# 06_SOM_Console.net
KiCad netlist of a schematic drawn in Altium Designer
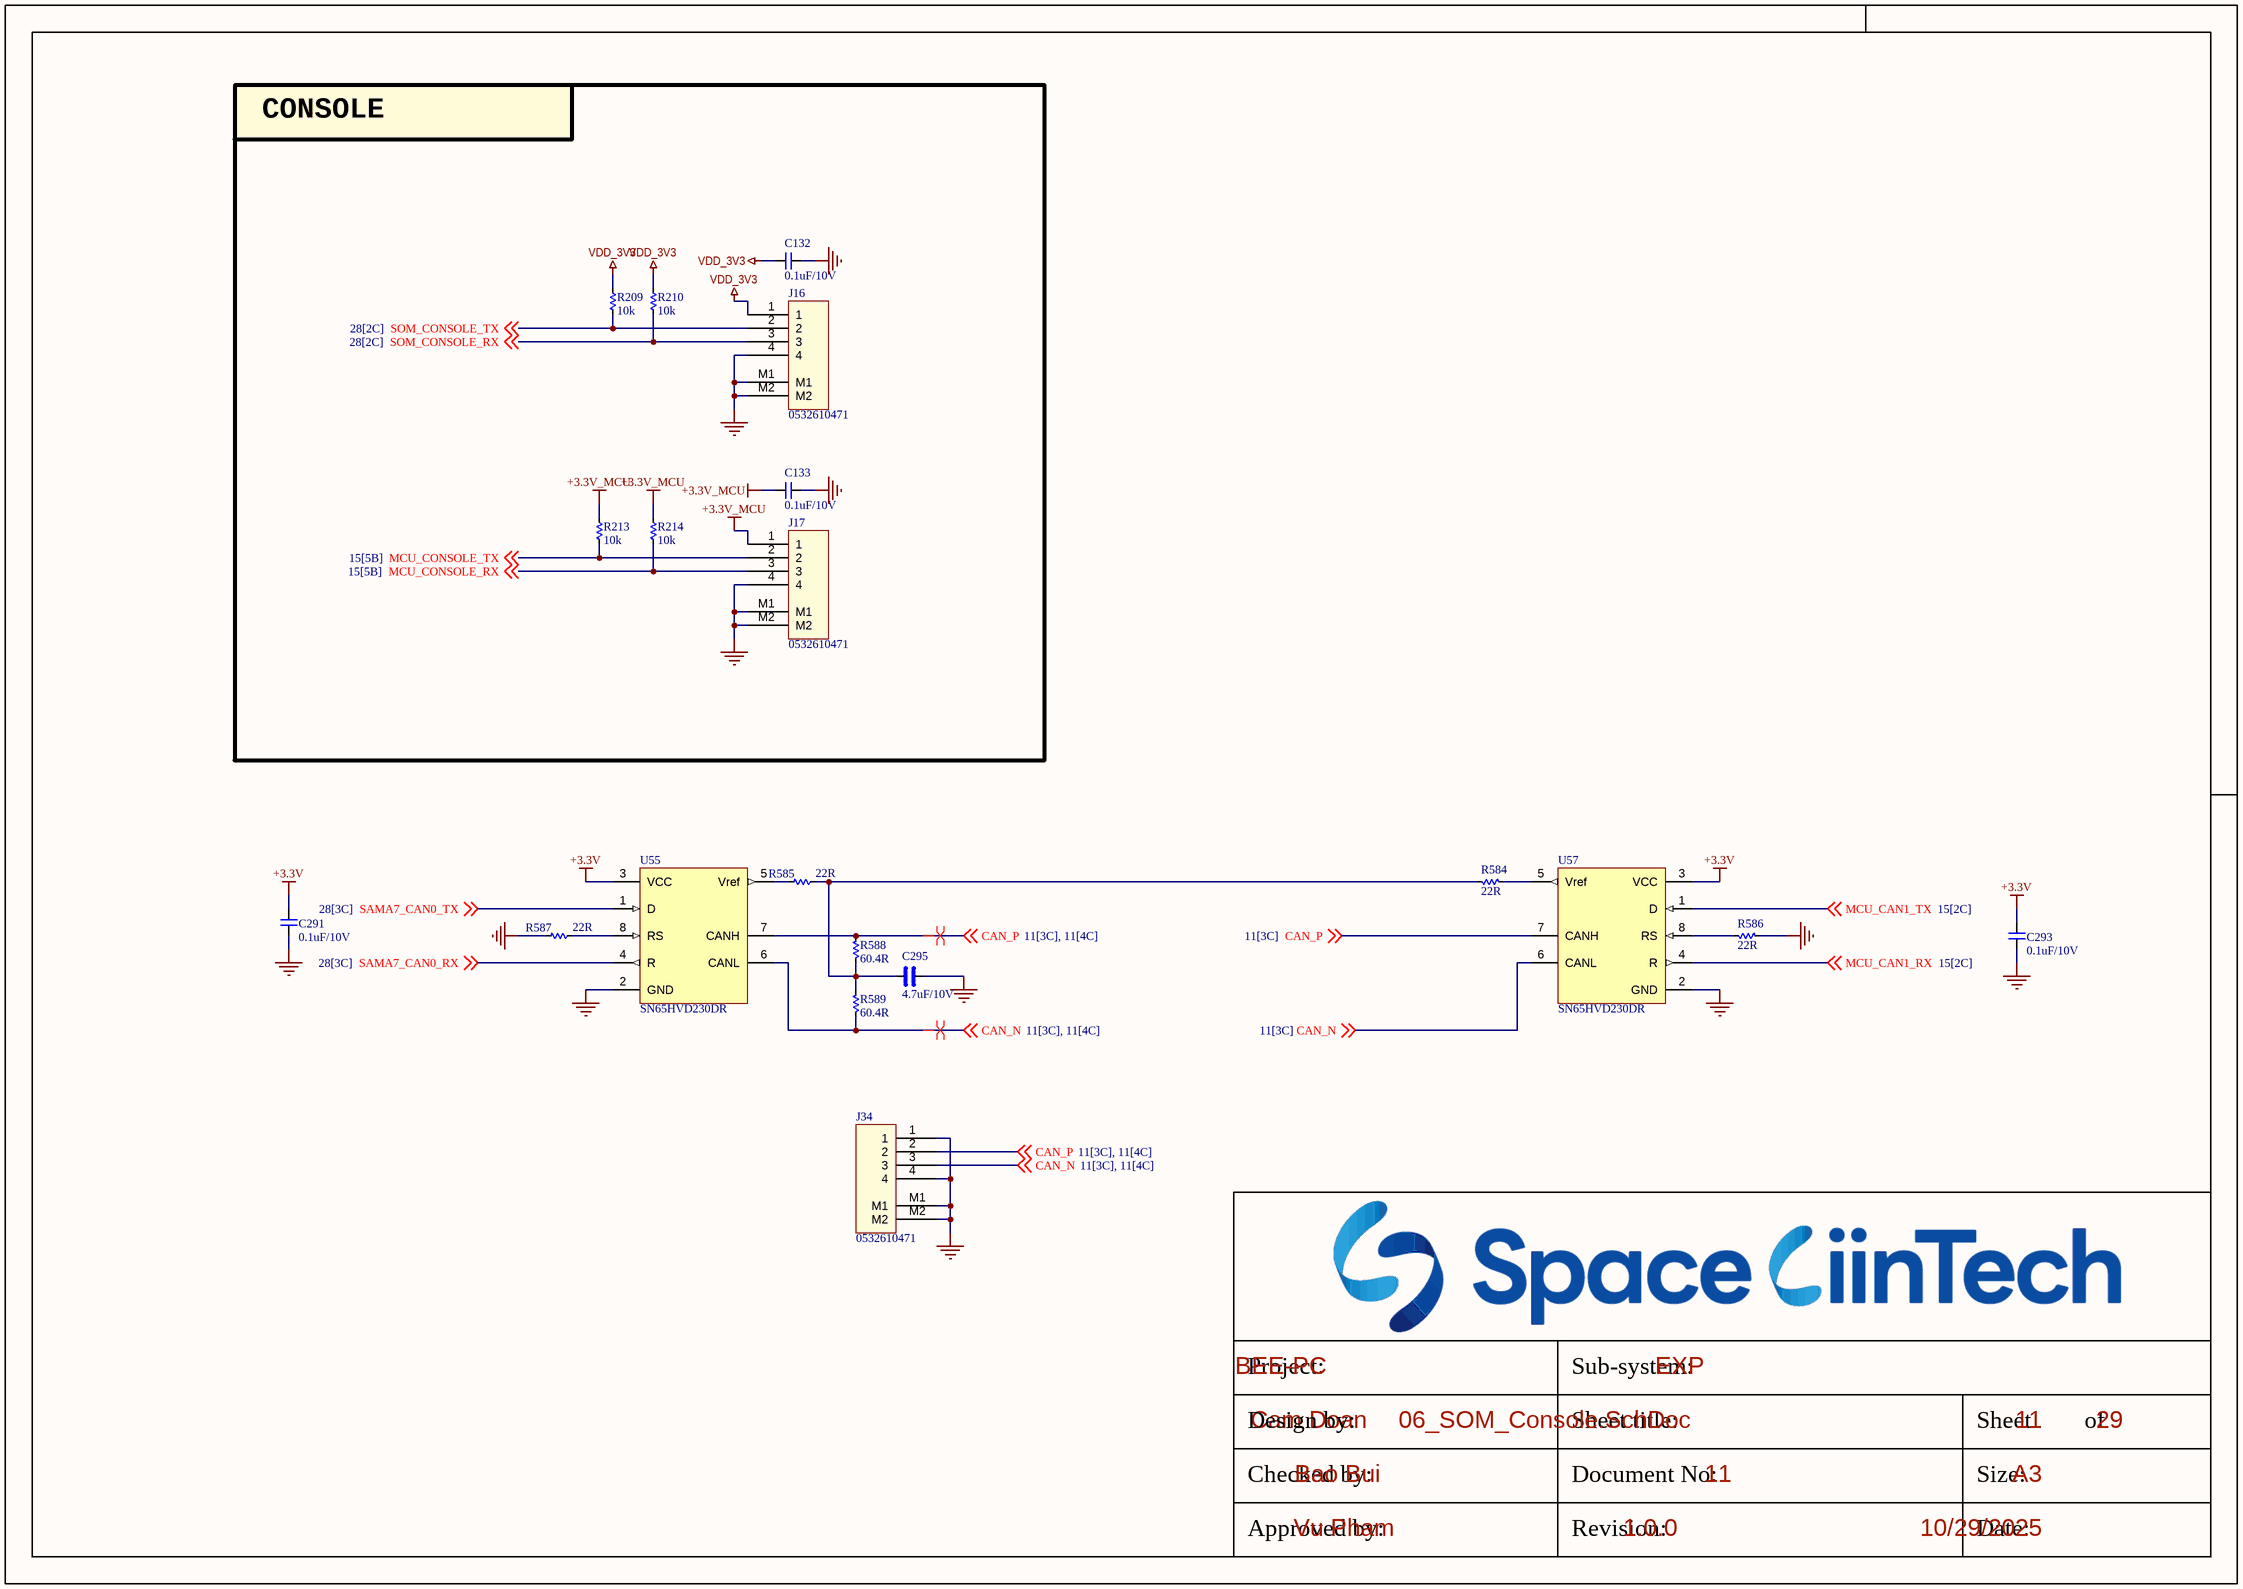
[diagram p0: 06_SOM_Console.SchDoc]

(export (version "E")
  (design (tool "Eeschema 10.0.6"))
  (components
    (comp (ref "C132")
      (value "0.1uF/10V")
      (footprint "CAP_C_1005X60")
      (description "CAP CHIP")
      (libsource (lib "LABLIB") (part "_CAP_C_2"))
    )
    (comp (ref "C133")
      (value "0.1uF/10V")
      (footprint "CAP_C_1005X60")
      (description "CAP CHIP")
      (libsource (lib "LABLIB") (part "_CAP_C_2"))
    )
    (comp (ref "C291")
      (value "0.1uF/10V")
      (footprint "CAP_C_1005X60")
      (description "CAP CHIP")
      (libsource (lib "LABLIB") (part "_CAP_C_2"))
    )
    (comp (ref "C293")
      (value "0.1uF/10V")
      (footprint "CAP_C_1005X60")
      (description "CAP CHIP")
      (libsource (lib "LABLIB") (part "_CAP_C_2"))
    )
    (comp (ref "C295")
      (value "4.7uF/10V")
      (footprint "CAP_C_1005X60")
      (description "CAP CHIP High Value")
      (libsource (lib "LABLIB") (part "_CAP_C_High_2"))
    )
    (comp (ref "J16")
      (value "0532610471")
      (footprint "MOLEX_0532610471")
      (libsource (lib "LABLIB") (part "Header 4x1_2M"))
    )
    (comp (ref "J17")
      (value "0532610471")
      (footprint "MOLEX_0532610471")
      (libsource (lib "LABLIB") (part "Header 4x1_2M"))
    )
    (comp (ref "J34")
      (value "0532610471")
      (footprint "MOLEX_0532610471")
      (libsource (lib "") (part "Header 4x1_2M_1"))
    )
    (comp (ref "R209")
      (value "10k")
      (footprint "RES_C_1005X40")
      (description "RES")
      (libsource (lib "LABLIB") (part "_RES_B_2"))
    )
    (comp (ref "R210")
      (value "10k")
      (footprint "RES_C_1005X40")
      (description "RES")
      (libsource (lib "LABLIB") (part "_RES_B_2"))
    )
    (comp (ref "R213")
      (value "10k")
      (footprint "RES_C_1005X40")
      (description "RES")
      (libsource (lib "LABLIB") (part "_RES_B_2"))
    )
    (comp (ref "R214")
      (value "10k")
      (footprint "RES_C_1005X40")
      (description "RES")
      (libsource (lib "LABLIB") (part "_RES_B_2"))
    )
    (comp (ref "R584")
      (value "22R")
      (footprint "RES_C_1005X40")
      (description "RES")
      (libsource (lib "LABLIB") (part "_RES_B_2"))
    )
    (comp (ref "R585")
      (value "22R")
      (footprint "RES_C_1005X40")
      (description "RES")
      (libsource (lib "LABLIB") (part "_RES_B_2"))
    )
    (comp (ref "R586")
      (value "22R")
      (footprint "RES_C_1005X40")
      (description "RES")
      (libsource (lib "LABLIB") (part "_RES_B_2"))
    )
    (comp (ref "R587")
      (value "22R")
      (footprint "RES_C_1005X40")
      (description "RES")
      (libsource (lib "LABLIB") (part "_RES_B_2"))
    )
    (comp (ref "R588")
      (value "60.4R")
      (footprint "RES_C_1005X40")
      (description "RES")
      (libsource (lib "LABLIB") (part "_RES_B_2"))
    )
    (comp (ref "R589")
      (value "60.4R")
      (footprint "RES_C_1005X40")
      (description "RES")
      (libsource (lib "LABLIB") (part "_RES_B_2"))
    )
    (comp (ref "U55")
      (value "SN65HVD230DR")
      (footprint "SOIC127P602X173-8N")
      (description "IC TRANSCEIVER HALF 1/1 8SOIC")
      (libsource (lib "LABLIB") (part "IC_CAN_SN65HVD230DR"))
    )
    (comp (ref "U57")
      (value "SN65HVD230DR")
      (footprint "SOIC127P602X173-8N")
      (description "IC TRANSCEIVER HALF 1/1 8SOIC")
      (libsource (lib "") (part "IC_CAN_SN65HVD230DR_1"))
    )
  )
  (nets
    (net (code "1") (name "+3.3V") (class "Default")
      (node (ref "C291") (pin "2") (pinfunction "2_2") (pintype "passive"))
      (node (ref "C293") (pin "2") (pinfunction "2_2") (pintype "passive"))
      (node (ref "U55") (pin "3") (pinfunction "VCC_3") (pintype "passive"))
      (node (ref "U57") (pin "3") (pinfunction "VCC_3") (pintype "passive"))
    )
    (net (code "2") (name "+3.3V_MCU") (class "Default")
      (node (ref "C133") (pin "2") (pinfunction "2_2") (pintype "passive"))
      (node (ref "J17") (pin "1") (pinfunction "1_1") (pintype "passive"))
      (node (ref "R213") (pin "2") (pinfunction "2_2") (pintype "passive"))
      (node (ref "R214") (pin "2") (pinfunction "2_2") (pintype "passive"))
    )
    (net (code "3") (name "CAN_N") (class "Default")
      (node (ref "J34") (pin "3") (pinfunction "3_3") (pintype "passive"))
      (node (ref "R589") (pin "1") (pinfunction "1_1") (pintype "passive"))
      (node (ref "U55") (pin "6") (pinfunction "CANL_6") (pintype "passive"))
      (node (ref "U57") (pin "6") (pinfunction "CANL_6") (pintype "passive"))
    )
    (net (code "4") (name "CAN_P") (class "Default")
      (node (ref "J34") (pin "2") (pinfunction "2_2") (pintype "passive"))
      (node (ref "R588") (pin "2") (pinfunction "2_2") (pintype "passive"))
      (node (ref "U55") (pin "7") (pinfunction "CANH_7") (pintype "passive"))
      (node (ref "U57") (pin "7") (pinfunction "CANH_7") (pintype "passive"))
    )
    (net (code "5") (name "GND") (class "Default")
      (node (ref "C132") (pin "1") (pinfunction "1_1") (pintype "passive"))
      (node (ref "C133") (pin "1") (pinfunction "1_1") (pintype "passive"))
      (node (ref "C291") (pin "1") (pinfunction "1_1") (pintype "passive"))
      (node (ref "C293") (pin "1") (pinfunction "1_1") (pintype "passive"))
      (node (ref "C295") (pin "1") (pinfunction "1_1") (pintype "passive"))
      (node (ref "J16") (pin "4") (pinfunction "4_4") (pintype "passive"))
      (node (ref "J16") (pin "M1") (pinfunction "M1_M1") (pintype "passive"))
      (node (ref "J16") (pin "M2") (pinfunction "M2_M2") (pintype "passive"))
      (node (ref "J17") (pin "4") (pinfunction "4_4") (pintype "passive"))
      (node (ref "J17") (pin "M1") (pinfunction "M1_M1") (pintype "passive"))
      (node (ref "J17") (pin "M2") (pinfunction "M2_M2") (pintype "passive"))
      (node (ref "J34") (pin "1") (pinfunction "1_1") (pintype "passive"))
      (node (ref "J34") (pin "4") (pinfunction "4_4") (pintype "passive"))
      (node (ref "J34") (pin "M1") (pinfunction "M1_M1") (pintype "passive"))
      (node (ref "J34") (pin "M2") (pinfunction "M2_M2") (pintype "passive"))
      (node (ref "R586") (pin "2") (pinfunction "2_2") (pintype "passive"))
      (node (ref "R587") (pin "2") (pinfunction "2_2") (pintype "passive"))
      (node (ref "U55") (pin "2") (pinfunction "GND_2") (pintype "passive"))
      (node (ref "U57") (pin "2") (pinfunction "GND_2") (pintype "passive"))
    )
    (net (code "6") (name "MCU_CAN1_RX") (class "Default")
      (node (ref "U57") (pin "4") (pinfunction "R_4") (pintype "output"))
    )
    (net (code "7") (name "MCU_CAN1_TX") (class "Default")
      (node (ref "U57") (pin "1") (pinfunction "D_1") (pintype "input"))
    )
    (net (code "8") (name "MCU_CONSOLE_RX") (class "Default")
      (node (ref "J17") (pin "3") (pinfunction "3_3") (pintype "passive"))
      (node (ref "R214") (pin "1") (pinfunction "1_1") (pintype "passive"))
    )
    (net (code "9") (name "MCU_CONSOLE_TX") (class "Default")
      (node (ref "J17") (pin "2") (pinfunction "2_2") (pintype "passive"))
      (node (ref "R213") (pin "1") (pinfunction "1_1") (pintype "passive"))
    )
    (net (code "10") (name "Net-(C295-Pad2)") (class "Default")
      (node (ref "C295") (pin "2") (pinfunction "2_2") (pintype "passive"))
      (node (ref "R584") (pin "1") (pinfunction "1_1") (pintype "passive"))
      (node (ref "R585") (pin "1") (pinfunction "1_1") (pintype "passive"))
      (node (ref "R588") (pin "1") (pinfunction "1_1") (pintype "passive"))
      (node (ref "R589") (pin "2") (pinfunction "2_2") (pintype "passive"))
    )
    (net (code "11") (name "Net-(U55-RS)") (class "Default")
      (node (ref "R587") (pin "1") (pinfunction "1_1") (pintype "passive"))
      (node (ref "U55") (pin "8") (pinfunction "RS_8") (pintype "input"))
    )
    (net (code "12") (name "Net-(U55-Vref)") (class "Default")
      (node (ref "R585") (pin "2") (pinfunction "2_2") (pintype "passive"))
      (node (ref "U55") (pin "5") (pinfunction "Vref_5") (pintype "output"))
    )
    (net (code "13") (name "Net-(U57-RS)") (class "Default")
      (node (ref "R586") (pin "1") (pinfunction "1_1") (pintype "passive"))
      (node (ref "U57") (pin "8") (pinfunction "RS_8") (pintype "input"))
    )
    (net (code "14") (name "Net-(U57-Vref)") (class "Default")
      (node (ref "R584") (pin "2") (pinfunction "2_2") (pintype "passive"))
      (node (ref "U57") (pin "5") (pinfunction "Vref_5") (pintype "output"))
    )
    (net (code "15") (name "SAMA7_CAN0_RX") (class "Default")
      (node (ref "U55") (pin "4") (pinfunction "R_4") (pintype "output"))
    )
    (net (code "16") (name "SAMA7_CAN0_TX") (class "Default")
      (node (ref "U55") (pin "1") (pinfunction "D_1") (pintype "input"))
    )
    (net (code "17") (name "SOM_CONSOLE_RX") (class "Default")
      (node (ref "J16") (pin "3") (pinfunction "3_3") (pintype "passive"))
      (node (ref "R210") (pin "1") (pinfunction "1_1") (pintype "passive"))
    )
    (net (code "18") (name "SOM_CONSOLE_TX") (class "Default")
      (node (ref "J16") (pin "2") (pinfunction "2_2") (pintype "passive"))
      (node (ref "R209") (pin "1") (pinfunction "1_1") (pintype "passive"))
    )
    (net (code "19") (name "VDD_3V3") (class "Default")
      (node (ref "C132") (pin "2") (pinfunction "2_2") (pintype "passive"))
      (node (ref "J16") (pin "1") (pinfunction "1_1") (pintype "passive"))
      (node (ref "R209") (pin "2") (pinfunction "2_2") (pintype "passive"))
      (node (ref "R210") (pin "2") (pinfunction "2_2") (pintype "passive"))
    )
  )
)
